# trig3_board_de0-nano.net
KiCad netlist of a schematic drawn in EAGLE
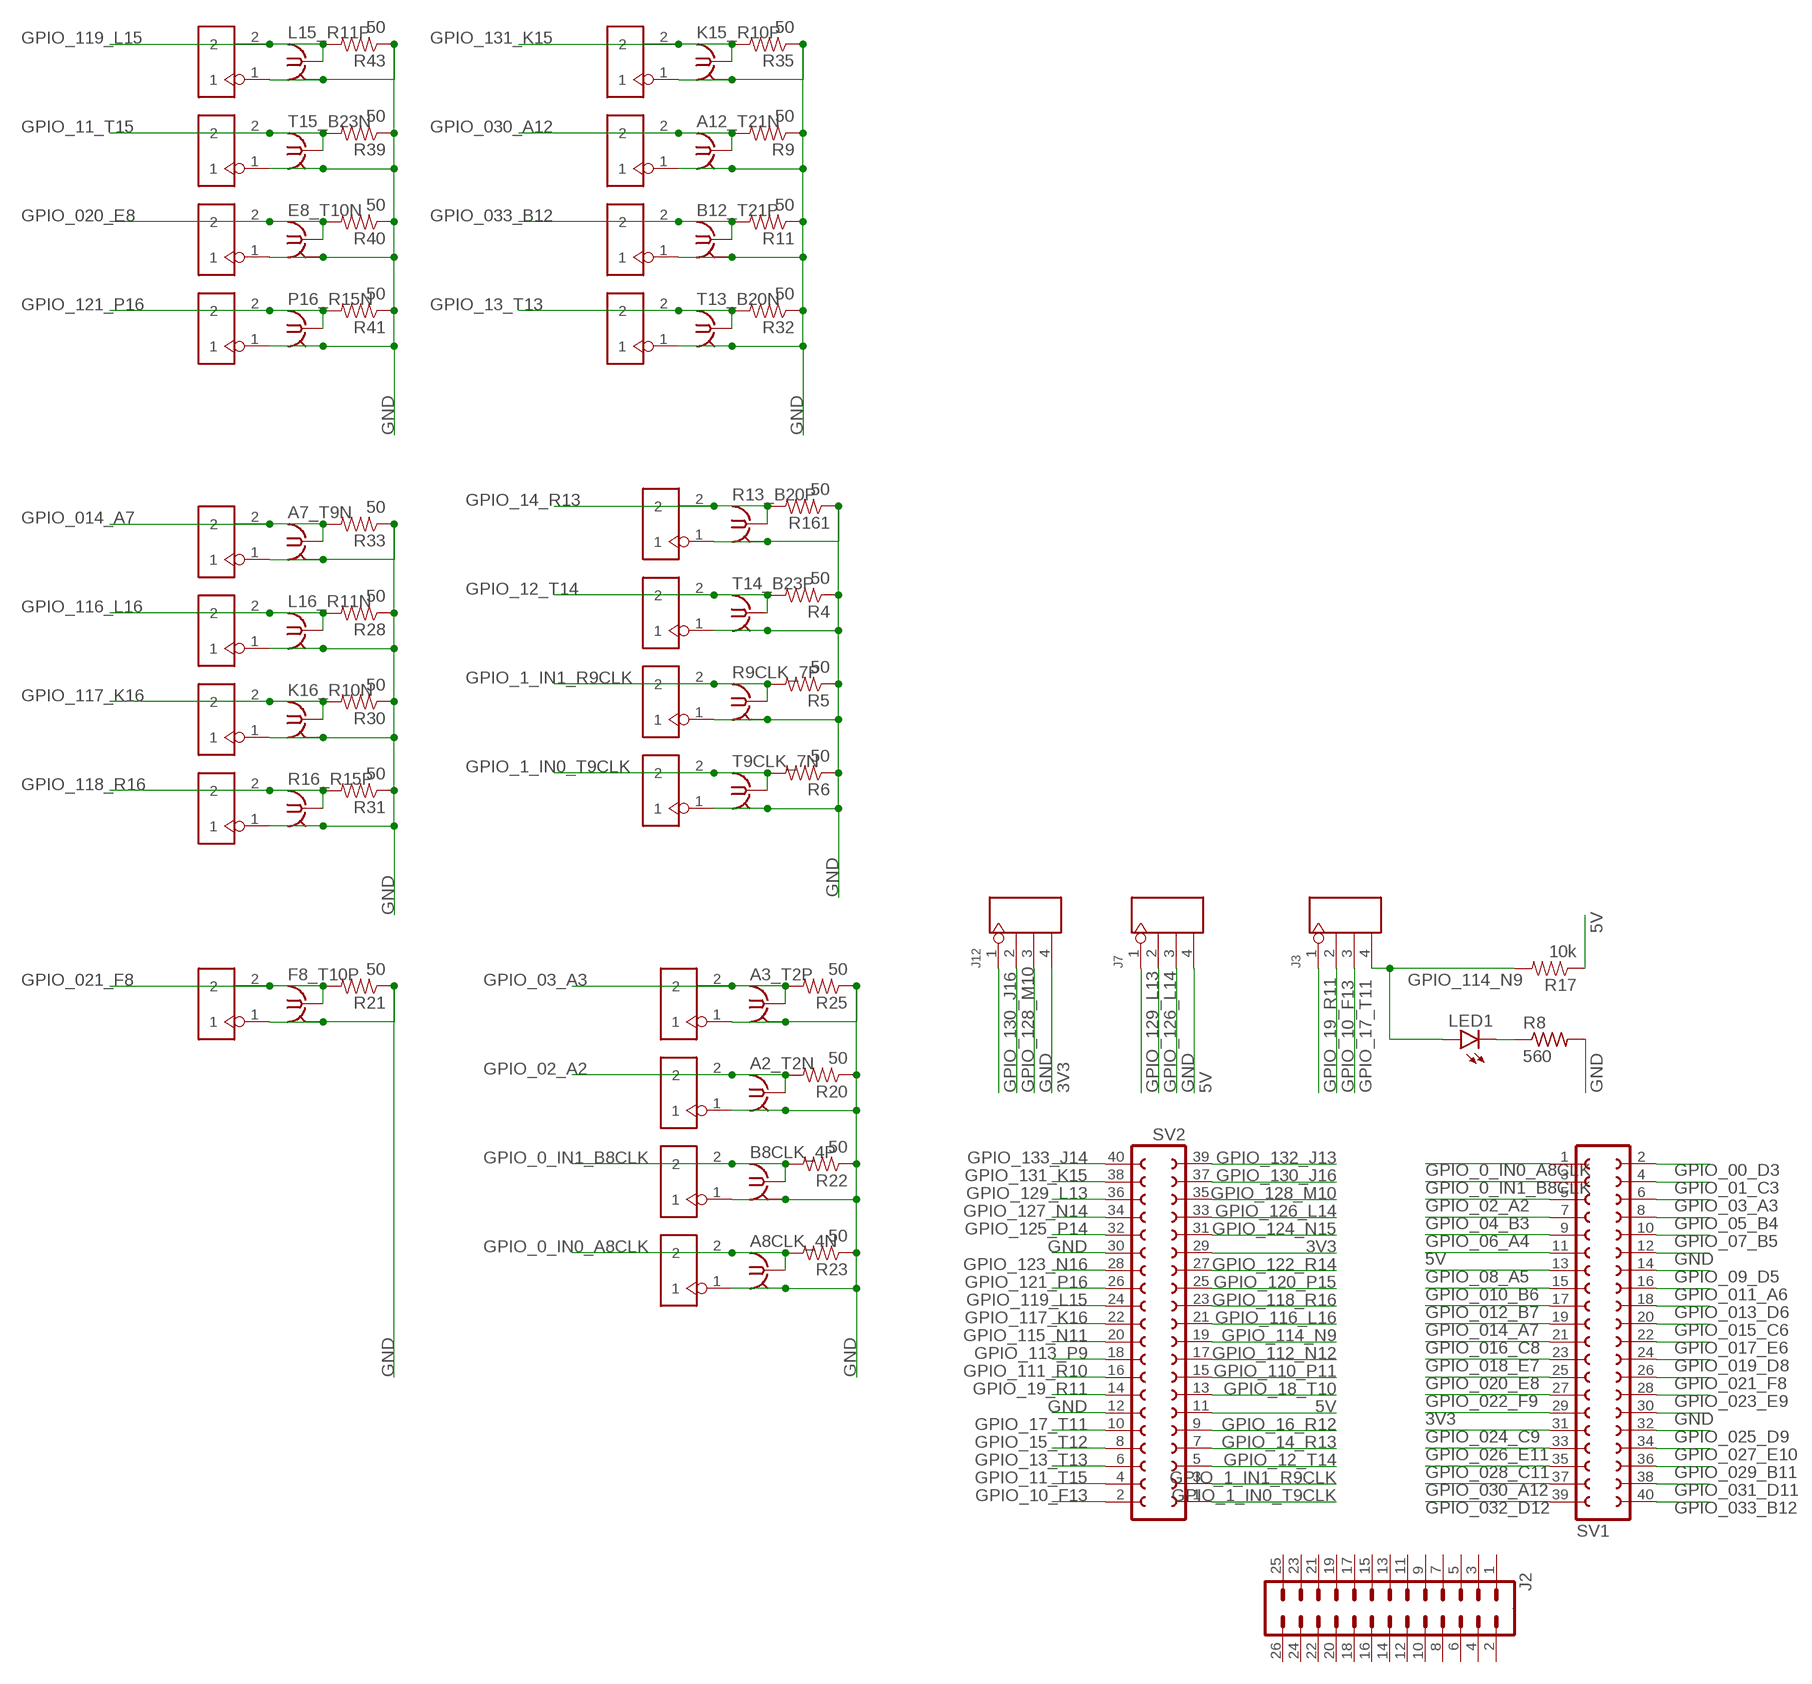
[diagram p0: schematic, sheet 1, part 1 of 2]
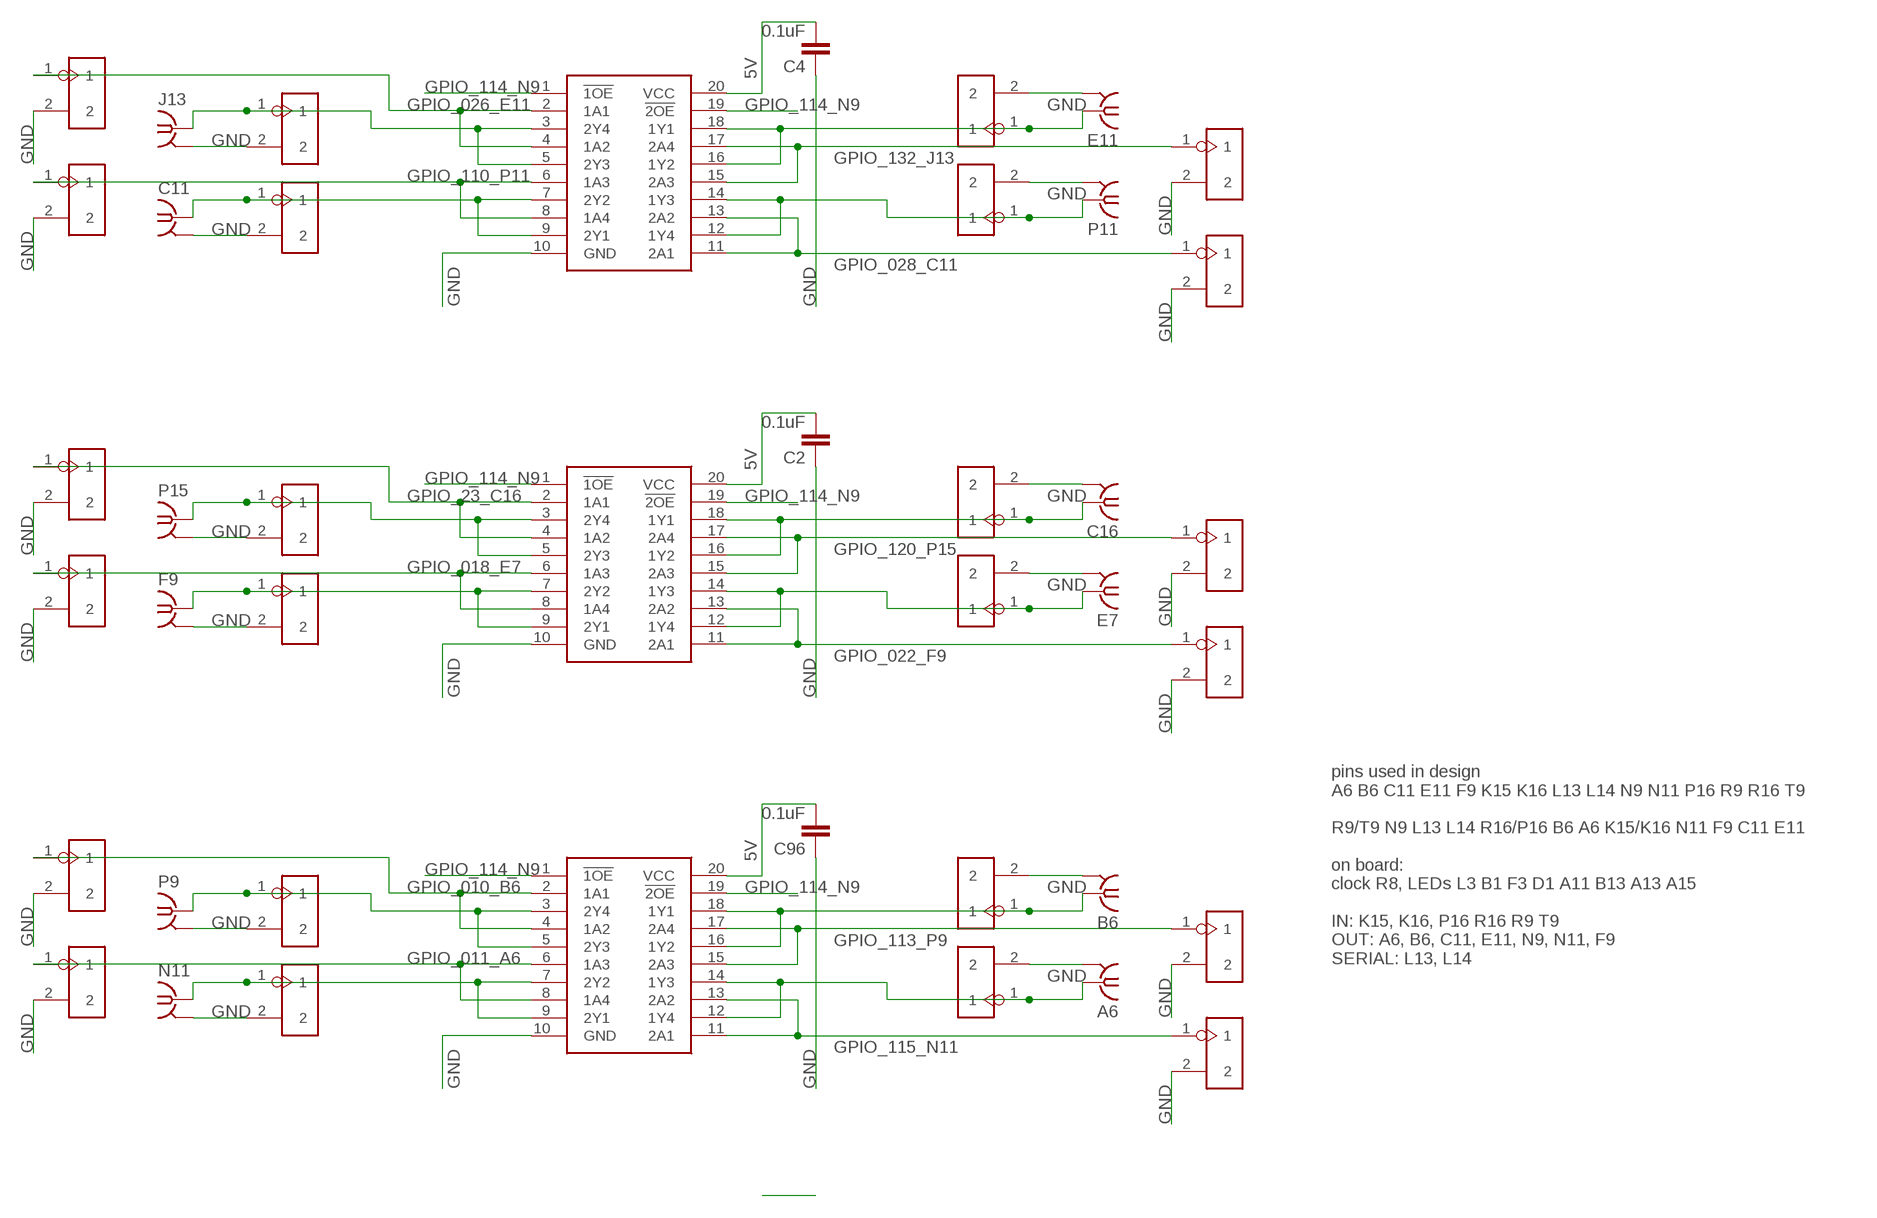
[diagram p1: schematic, sheet 1, part 2 of 2]

(export (version "E")
  (design (tool "Eeschema 10.0.6"))
  (components
    (comp (ref "A2_T2N")
      (value "BU-SMB-V")
      (footprint "eagle-import:BU-SMB-V")
      (libsource (lib "eagle-import") (part "BU-SMB-V"))
    )
    (comp (ref "A3_T2P")
      (value "BU-SMB-V")
      (footprint "eagle-import:BU-SMB-V")
      (libsource (lib "eagle-import") (part "BU-SMB-V"))
    )
    (comp (ref "A6")
      (value "BU-SMB-V")
      (footprint "eagle-import:BU-SMB-V")
      (libsource (lib "eagle-import") (part "BU-SMB-V"))
    )
    (comp (ref "A7_T9N")
      (value "BU-SMB-V")
      (footprint "eagle-import:BU-SMB-V")
      (libsource (lib "eagle-import") (part "BU-SMB-V"))
    )
    (comp (ref "A8CLK_4N")
      (value "BU-SMB-V")
      (footprint "eagle-import:BU-SMB-V")
      (libsource (lib "eagle-import") (part "BU-SMB-V"))
    )
    (comp (ref "A12_T21N")
      (value "BU-SMB-V")
      (footprint "eagle-import:BU-SMB-V")
      (libsource (lib "eagle-import") (part "BU-SMB-V"))
    )
    (comp (ref "B6")
      (value "BU-SMB-V")
      (footprint "eagle-import:BU-SMB-V")
      (libsource (lib "eagle-import") (part "BU-SMB-V"))
    )
    (comp (ref "B8CLK_4P")
      (value "BU-SMB-V")
      (footprint "eagle-import:BU-SMB-V")
      (libsource (lib "eagle-import") (part "BU-SMB-V"))
    )
    (comp (ref "B12_T21P")
      (value "BU-SMB-V")
      (footprint "eagle-import:BU-SMB-V")
      (libsource (lib "eagle-import") (part "BU-SMB-V"))
    )
    (comp (ref "C2")
      (value "0.1uF")
      (footprint "eagle-import:0805")
      (libsource (lib "eagle-import") (part "CAP0805"))
    )
    (comp (ref "C4")
      (value "0.1uF")
      (footprint "eagle-import:0805")
      (libsource (lib "eagle-import") (part "CAP0805"))
    )
    (comp (ref "C11")
      (value "BU-SMB-V")
      (footprint "eagle-import:BU-SMB-V")
      (libsource (lib "eagle-import") (part "BU-SMB-V"))
    )
    (comp (ref "C16")
      (value "BU-SMB-V")
      (footprint "eagle-import:BU-SMB-V")
      (libsource (lib "eagle-import") (part "BU-SMB-V"))
    )
    (comp (ref "C96")
      (value "0.1uF")
      (footprint "eagle-import:0805")
      (libsource (lib "eagle-import") (part "CAP0805"))
    )
    (comp (ref "E7")
      (value "BU-SMB-V")
      (footprint "eagle-import:BU-SMB-V")
      (libsource (lib "eagle-import") (part "BU-SMB-V"))
    )
    (comp (ref "E8_T10N")
      (value "BU-SMB-V")
      (footprint "eagle-import:BU-SMB-V")
      (libsource (lib "eagle-import") (part "BU-SMB-V"))
    )
    (comp (ref "E11")
      (value "BU-SMB-V")
      (footprint "eagle-import:BU-SMB-V")
      (libsource (lib "eagle-import") (part "BU-SMB-V"))
    )
    (comp (ref "F8_T10P")
      (value "BU-SMB-V")
      (footprint "eagle-import:BU-SMB-V")
      (libsource (lib "eagle-import") (part "BU-SMB-V"))
    )
    (comp (ref "F9")
      (value "BU-SMB-V")
      (footprint "eagle-import:BU-SMB-V")
      (libsource (lib "eagle-import") (part "BU-SMB-V"))
    )
    (comp (ref "J2")
      (value "M13X22X13")
      (footprint "eagle-import:2X13")
      (libsource (lib "eagle-import") (part "M13X22X13"))
    )
    (comp (ref "J3")
      (value "4p-2.54")
      (footprint "eagle-import:H4-2.54")
      (fields (field (name "MPN") "F185-1104A1BSYA1"))
      (libsource (lib "eagle-import") (part "DIP-BLACK-FEMALE-HEADER-VERT(4P-2.54)"))
    )
    (comp (ref "J4")
      (value "2p-2.54")
      (footprint "eagle-import:H2-2.54")
      (fields (field (name "MPN") "P125-1102A0BS116A1"))
      (libsource (lib "eagle-import") (part "DIP-BLACK-MALE-HEADER-VERT(2P-2.54)"))
    )
    (comp (ref "J5")
      (value "2p-2.54")
      (footprint "eagle-import:H2-2.54")
      (fields (field (name "MPN") "P125-1102A0BS116A1"))
      (libsource (lib "eagle-import") (part "DIP-BLACK-MALE-HEADER-VERT(2P-2.54)"))
    )
    (comp (ref "J6")
      (value "2p-2.54")
      (footprint "eagle-import:H2-2.54")
      (fields (field (name "MPN") "P125-1102A0BS116A1"))
      (libsource (lib "eagle-import") (part "DIP-BLACK-MALE-HEADER-VERT(2P-2.54)"))
    )
    (comp (ref "J7")
      (value "4p-2.54")
      (footprint "eagle-import:H4-2.54")
      (fields (field (name "MPN") "F185-1104A1BSYA1"))
      (libsource (lib "eagle-import") (part "DIP-BLACK-FEMALE-HEADER-VERT(4P-2.54)"))
    )
    (comp (ref "J12")
      (value "4p-2.54")
      (footprint "eagle-import:H4-2.54")
      (fields (field (name "MPN") "F185-1104A1BSYA1"))
      (libsource (lib "eagle-import") (part "DIP-BLACK-FEMALE-HEADER-VERT(4P-2.54)"))
    )
    (comp (ref "J13")
      (value "BU-SMB-V")
      (footprint "eagle-import:BU-SMB-V")
      (libsource (lib "eagle-import") (part "BU-SMB-V"))
    )
    (comp (ref "J17")
      (value "2p-2.54")
      (footprint "eagle-import:H2-2.54")
      (fields (field (name "MPN") "P125-1102A0BS116A1"))
      (libsource (lib "eagle-import") (part "DIP-BLACK-MALE-HEADER-VERT(2P-2.54)"))
    )
    (comp (ref "J18")
      (value "2p-2.54")
      (footprint "eagle-import:H2-2.54")
      (fields (field (name "MPN") "P125-1102A0BS116A1"))
      (libsource (lib "eagle-import") (part "DIP-BLACK-MALE-HEADER-VERT(2P-2.54)"))
    )
    (comp (ref "J22")
      (value "2p-2.54")
      (footprint "eagle-import:H2-2.54")
      (fields (field (name "MPN") "P125-1102A0BS116A1"))
      (libsource (lib "eagle-import") (part "DIP-BLACK-MALE-HEADER-VERT(2P-2.54)"))
    )
    (comp (ref "J23")
      (value "2p-2.54")
      (footprint "eagle-import:H2-2.54")
      (fields (field (name "MPN") "P125-1102A0BS116A1"))
      (libsource (lib "eagle-import") (part "DIP-BLACK-MALE-HEADER-VERT(2P-2.54)"))
    )
    (comp (ref "J24")
      (value "2p-2.54")
      (footprint "eagle-import:H2-2.54")
      (fields (field (name "MPN") "P125-1102A0BS116A1"))
      (libsource (lib "eagle-import") (part "DIP-BLACK-MALE-HEADER-VERT(2P-2.54)"))
    )
    (comp (ref "J25")
      (value "2p-2.54")
      (footprint "eagle-import:H2-2.54")
      (fields (field (name "MPN") "P125-1102A0BS116A1"))
      (libsource (lib "eagle-import") (part "DIP-BLACK-MALE-HEADER-VERT(2P-2.54)"))
    )
    (comp (ref "J32")
      (value "2p-2.54")
      (footprint "eagle-import:H2-2.54")
      (fields (field (name "MPN") "P125-1102A0BS116A1"))
      (libsource (lib "eagle-import") (part "DIP-BLACK-MALE-HEADER-VERT(2P-2.54)"))
    )
    (comp (ref "J33")
      (value "2p-2.54")
      (footprint "eagle-import:H2-2.54")
      (fields (field (name "MPN") "P125-1102A0BS116A1"))
      (libsource (lib "eagle-import") (part "DIP-BLACK-MALE-HEADER-VERT(2P-2.54)"))
    )
    (comp (ref "J34")
      (value "2p-2.54")
      (footprint "eagle-import:H2-2.54")
      (fields (field (name "MPN") "P125-1102A0BS116A1"))
      (libsource (lib "eagle-import") (part "DIP-BLACK-MALE-HEADER-VERT(2P-2.54)"))
    )
    (comp (ref "J35")
      (value "2p-2.54")
      (footprint "eagle-import:H2-2.54")
      (fields (field (name "MPN") "P125-1102A0BS116A1"))
      (libsource (lib "eagle-import") (part "DIP-BLACK-MALE-HEADER-VERT(2P-2.54)"))
    )
    (comp (ref "J36")
      (value "2p-2.54")
      (footprint "eagle-import:H2-2.54")
      (fields (field (name "MPN") "P125-1102A0BS116A1"))
      (libsource (lib "eagle-import") (part "DIP-BLACK-MALE-HEADER-VERT(2P-2.54)"))
    )
    (comp (ref "J37")
      (value "2p-2.54")
      (footprint "eagle-import:H2-2.54")
      (fields (field (name "MPN") "P125-1102A0BS116A1"))
      (libsource (lib "eagle-import") (part "DIP-BLACK-MALE-HEADER-VERT(2P-2.54)"))
    )
    (comp (ref "J38")
      (value "2p-2.54")
      (footprint "eagle-import:H2-2.54")
      (fields (field (name "MPN") "P125-1102A0BS116A1"))
      (libsource (lib "eagle-import") (part "DIP-BLACK-MALE-HEADER-VERT(2P-2.54)"))
    )
    (comp (ref "J39")
      (value "2p-2.54")
      (footprint "eagle-import:H2-2.54")
      (fields (field (name "MPN") "P125-1102A0BS116A1"))
      (libsource (lib "eagle-import") (part "DIP-BLACK-MALE-HEADER-VERT(2P-2.54)"))
    )
    (comp (ref "J40")
      (value "2p-2.54")
      (footprint "eagle-import:H2-2.54")
      (fields (field (name "MPN") "P125-1102A0BS116A1"))
      (libsource (lib "eagle-import") (part "DIP-BLACK-MALE-HEADER-VERT(2P-2.54)"))
    )
    (comp (ref "J41")
      (value "2p-2.54")
      (footprint "eagle-import:H2-2.54")
      (fields (field (name "MPN") "P125-1102A0BS116A1"))
      (libsource (lib "eagle-import") (part "DIP-BLACK-MALE-HEADER-VERT(2P-2.54)"))
    )
    (comp (ref "J42")
      (value "2p-2.54")
      (footprint "eagle-import:H2-2.54")
      (fields (field (name "MPN") "P125-1102A0BS116A1"))
      (libsource (lib "eagle-import") (part "DIP-BLACK-MALE-HEADER-VERT(2P-2.54)"))
    )
    (comp (ref "J43")
      (value "2p-2.54")
      (footprint "eagle-import:H2-2.54")
      (fields (field (name "MPN") "P125-1102A0BS116A1"))
      (libsource (lib "eagle-import") (part "DIP-BLACK-MALE-HEADER-VERT(2P-2.54)"))
    )
    (comp (ref "K15_R10P")
      (value "BU-SMB-V")
      (footprint "eagle-import:BU-SMB-V")
      (libsource (lib "eagle-import") (part "BU-SMB-V"))
    )
    (comp (ref "K16_R10N")
      (value "BU-SMB-V")
      (footprint "eagle-import:BU-SMB-V")
      (libsource (lib "eagle-import") (part "BU-SMB-V"))
    )
    (comp (ref "L15_R11P")
      (value "BU-SMB-V")
      (footprint "eagle-import:BU-SMB-V")
      (libsource (lib "eagle-import") (part "BU-SMB-V"))
    )
    (comp (ref "L16_R11N")
      (value "BU-SMB-V")
      (footprint "eagle-import:BU-SMB-V")
      (libsource (lib "eagle-import") (part "BU-SMB-V"))
    )
    (comp (ref "LED1")
      (value "red")
      (footprint "eagle-import:CHIP-LED0805")
      (libsource (lib "eagle-import") (part "LEDCHIP-LED0805"))
    )
    (comp (ref "N11")
      (value "BU-SMB-V")
      (footprint "eagle-import:BU-SMB-V")
      (libsource (lib "eagle-import") (part "BU-SMB-V"))
    )
    (comp (ref "OJ41")
      (value "2p-2.54")
      (footprint "eagle-import:H2-2.54")
      (fields (field (name "MPN") "P125-1102A0BS116A1"))
      (libsource (lib "eagle-import") (part "DIP-BLACK-MALE-HEADER-VERT(2P-2.54)"))
    )
    (comp (ref "OJ42")
      (value "2p-2.54")
      (footprint "eagle-import:H2-2.54")
      (fields (field (name "MPN") "P125-1102A0BS116A1"))
      (libsource (lib "eagle-import") (part "DIP-BLACK-MALE-HEADER-VERT(2P-2.54)"))
    )
    (comp (ref "OJ43")
      (value "2p-2.54")
      (footprint "eagle-import:H2-2.54")
      (fields (field (name "MPN") "P125-1102A0BS116A1"))
      (libsource (lib "eagle-import") (part "DIP-BLACK-MALE-HEADER-VERT(2P-2.54)"))
    )
    (comp (ref "OJ44")
      (value "2p-2.54")
      (footprint "eagle-import:H2-2.54")
      (fields (field (name "MPN") "P125-1102A0BS116A1"))
      (libsource (lib "eagle-import") (part "DIP-BLACK-MALE-HEADER-VERT(2P-2.54)"))
    )
    (comp (ref "OJ45")
      (value "2p-2.54")
      (footprint "eagle-import:H2-2.54")
      (fields (field (name "MPN") "P125-1102A0BS116A1"))
      (libsource (lib "eagle-import") (part "DIP-BLACK-MALE-HEADER-VERT(2P-2.54)"))
    )
    (comp (ref "OJ46")
      (value "2p-2.54")
      (footprint "eagle-import:H2-2.54")
      (fields (field (name "MPN") "P125-1102A0BS116A1"))
      (libsource (lib "eagle-import") (part "DIP-BLACK-MALE-HEADER-VERT(2P-2.54)"))
    )
    (comp (ref "OJ47")
      (value "2p-2.54")
      (footprint "eagle-import:H2-2.54")
      (fields (field (name "MPN") "P125-1102A0BS116A1"))
      (libsource (lib "eagle-import") (part "DIP-BLACK-MALE-HEADER-VERT(2P-2.54)"))
    )
    (comp (ref "OJ48")
      (value "2p-2.54")
      (footprint "eagle-import:H2-2.54")
      (fields (field (name "MPN") "P125-1102A0BS116A1"))
      (libsource (lib "eagle-import") (part "DIP-BLACK-MALE-HEADER-VERT(2P-2.54)"))
    )
    (comp (ref "OJ57")
      (value "2p-2.54")
      (footprint "eagle-import:H2-2.54")
      (fields (field (name "MPN") "P125-1102A0BS116A1"))
      (libsource (lib "eagle-import") (part "DIP-BLACK-MALE-HEADER-VERT(2P-2.54)"))
    )
    (comp (ref "OJ58")
      (value "2p-2.54")
      (footprint "eagle-import:H2-2.54")
      (fields (field (name "MPN") "P125-1102A0BS116A1"))
      (libsource (lib "eagle-import") (part "DIP-BLACK-MALE-HEADER-VERT(2P-2.54)"))
    )
    (comp (ref "OJ59")
      (value "2p-2.54")
      (footprint "eagle-import:H2-2.54")
      (fields (field (name "MPN") "P125-1102A0BS116A1"))
      (libsource (lib "eagle-import") (part "DIP-BLACK-MALE-HEADER-VERT(2P-2.54)"))
    )
    (comp (ref "OJ60")
      (value "2p-2.54")
      (footprint "eagle-import:H2-2.54")
      (fields (field (name "MPN") "P125-1102A0BS116A1"))
      (libsource (lib "eagle-import") (part "DIP-BLACK-MALE-HEADER-VERT(2P-2.54)"))
    )
    (comp (ref "OJ61")
      (value "2p-2.54")
      (footprint "eagle-import:H2-2.54")
      (fields (field (name "MPN") "P125-1102A0BS116A1"))
      (libsource (lib "eagle-import") (part "DIP-BLACK-MALE-HEADER-VERT(2P-2.54)"))
    )
    (comp (ref "OJ62")
      (value "2p-2.54")
      (footprint "eagle-import:H2-2.54")
      (fields (field (name "MPN") "P125-1102A0BS116A1"))
      (libsource (lib "eagle-import") (part "DIP-BLACK-MALE-HEADER-VERT(2P-2.54)"))
    )
    (comp (ref "OJ63")
      (value "2p-2.54")
      (footprint "eagle-import:H2-2.54")
      (fields (field (name "MPN") "P125-1102A0BS116A1"))
      (libsource (lib "eagle-import") (part "DIP-BLACK-MALE-HEADER-VERT(2P-2.54)"))
    )
    (comp (ref "OJ64")
      (value "2p-2.54")
      (footprint "eagle-import:H2-2.54")
      (fields (field (name "MPN") "P125-1102A0BS116A1"))
      (libsource (lib "eagle-import") (part "DIP-BLACK-MALE-HEADER-VERT(2P-2.54)"))
    )
    (comp (ref "OJ73")
      (value "2p-2.54")
      (footprint "eagle-import:H2-2.54")
      (fields (field (name "MPN") "P125-1102A0BS116A1"))
      (libsource (lib "eagle-import") (part "DIP-BLACK-MALE-HEADER-VERT(2P-2.54)"))
    )
    (comp (ref "OJ74")
      (value "2p-2.54")
      (footprint "eagle-import:H2-2.54")
      (fields (field (name "MPN") "P125-1102A0BS116A1"))
      (libsource (lib "eagle-import") (part "DIP-BLACK-MALE-HEADER-VERT(2P-2.54)"))
    )
    (comp (ref "OJ75")
      (value "2p-2.54")
      (footprint "eagle-import:H2-2.54")
      (fields (field (name "MPN") "P125-1102A0BS116A1"))
      (libsource (lib "eagle-import") (part "DIP-BLACK-MALE-HEADER-VERT(2P-2.54)"))
    )
    (comp (ref "OJ76")
      (value "2p-2.54")
      (footprint "eagle-import:H2-2.54")
      (fields (field (name "MPN") "P125-1102A0BS116A1"))
      (libsource (lib "eagle-import") (part "DIP-BLACK-MALE-HEADER-VERT(2P-2.54)"))
    )
    (comp (ref "OJ77")
      (value "2p-2.54")
      (footprint "eagle-import:H2-2.54")
      (fields (field (name "MPN") "P125-1102A0BS116A1"))
      (libsource (lib "eagle-import") (part "DIP-BLACK-MALE-HEADER-VERT(2P-2.54)"))
    )
    (comp (ref "OJ78")
      (value "2p-2.54")
      (footprint "eagle-import:H2-2.54")
      (fields (field (name "MPN") "P125-1102A0BS116A1"))
      (libsource (lib "eagle-import") (part "DIP-BLACK-MALE-HEADER-VERT(2P-2.54)"))
    )
    (comp (ref "OJ79")
      (value "2p-2.54")
      (footprint "eagle-import:H2-2.54")
      (fields (field (name "MPN") "P125-1102A0BS116A1"))
      (libsource (lib "eagle-import") (part "DIP-BLACK-MALE-HEADER-VERT(2P-2.54)"))
    )
    (comp (ref "OJ80")
      (value "2p-2.54")
      (footprint "eagle-import:H2-2.54")
      (fields (field (name "MPN") "P125-1102A0BS116A1"))
      (libsource (lib "eagle-import") (part "DIP-BLACK-MALE-HEADER-VERT(2P-2.54)"))
    )
    (comp (ref "P9")
      (value "BU-SMB-V")
      (footprint "eagle-import:BU-SMB-V")
      (libsource (lib "eagle-import") (part "BU-SMB-V"))
    )
    (comp (ref "P11")
      (value "BU-SMB-V")
      (footprint "eagle-import:BU-SMB-V")
      (libsource (lib "eagle-import") (part "BU-SMB-V"))
    )
    (comp (ref "P15")
      (value "BU-SMB-V")
      (footprint "eagle-import:BU-SMB-V")
      (libsource (lib "eagle-import") (part "BU-SMB-V"))
    )
    (comp (ref "P16_R15N")
      (value "BU-SMB-V")
      (footprint "eagle-import:BU-SMB-V")
      (libsource (lib "eagle-import") (part "BU-SMB-V"))
    )
    (comp (ref "R4")
      (value "50")
      (footprint "eagle-import:AXIAL-0.3")
      (libsource (lib "eagle-import") (part "RESISTORAXIAL-0.3"))
    )
    (comp (ref "R5")
      (value "50")
      (footprint "eagle-import:AXIAL-0.3")
      (libsource (lib "eagle-import") (part "RESISTORAXIAL-0.3"))
    )
    (comp (ref "R6")
      (value "50")
      (footprint "eagle-import:AXIAL-0.3")
      (libsource (lib "eagle-import") (part "RESISTORAXIAL-0.3"))
    )
    (comp (ref "R8")
      (value "560")
      (footprint "eagle-import:R0805")
      (libsource (lib "eagle-import") (part "R-US_R0805"))
    )
    (comp (ref "R9")
      (value "50")
      (footprint "eagle-import:AXIAL-0.3")
      (libsource (lib "eagle-import") (part "RESISTORAXIAL-0.3"))
    )
    (comp (ref "R9CLK_7P")
      (value "BU-SMB-V")
      (footprint "eagle-import:BU-SMB-V")
      (libsource (lib "eagle-import") (part "BU-SMB-V"))
    )
    (comp (ref "R11")
      (value "50")
      (footprint "eagle-import:AXIAL-0.3")
      (libsource (lib "eagle-import") (part "RESISTORAXIAL-0.3"))
    )
    (comp (ref "R13_B20P")
      (value "BU-SMB-V")
      (footprint "eagle-import:BU-SMB-V")
      (libsource (lib "eagle-import") (part "BU-SMB-V"))
    )
    (comp (ref "R16_R15P")
      (value "BU-SMB-V")
      (footprint "eagle-import:BU-SMB-V")
      (libsource (lib "eagle-import") (part "BU-SMB-V"))
    )
    (comp (ref "R17")
      (value "10k")
      (footprint "eagle-import:AXIAL-0.3")
      (libsource (lib "eagle-import") (part "RESISTORAXIAL-0.3"))
    )
    (comp (ref "R20")
      (value "50")
      (footprint "eagle-import:AXIAL-0.3")
      (libsource (lib "eagle-import") (part "RESISTORAXIAL-0.3"))
    )
    (comp (ref "R21")
      (value "50")
      (footprint "eagle-import:AXIAL-0.3")
      (libsource (lib "eagle-import") (part "RESISTORAXIAL-0.3"))
    )
    (comp (ref "R22")
      (value "50")
      (footprint "eagle-import:AXIAL-0.3")
      (libsource (lib "eagle-import") (part "RESISTORAXIAL-0.3"))
    )
    (comp (ref "R23")
      (value "50")
      (footprint "eagle-import:AXIAL-0.3")
      (libsource (lib "eagle-import") (part "RESISTORAXIAL-0.3"))
    )
    (comp (ref "R25")
      (value "50")
      (footprint "eagle-import:AXIAL-0.3")
      (libsource (lib "eagle-import") (part "RESISTORAXIAL-0.3"))
    )
    (comp (ref "R28")
      (value "50")
      (footprint "eagle-import:AXIAL-0.3")
      (libsource (lib "eagle-import") (part "RESISTORAXIAL-0.3"))
    )
    (comp (ref "R30")
      (value "50")
      (footprint "eagle-import:AXIAL-0.3")
      (libsource (lib "eagle-import") (part "RESISTORAXIAL-0.3"))
    )
    (comp (ref "R31")
      (value "50")
      (footprint "eagle-import:AXIAL-0.3")
      (libsource (lib "eagle-import") (part "RESISTORAXIAL-0.3"))
    )
    (comp (ref "R32")
      (value "50")
      (footprint "eagle-import:AXIAL-0.3")
      (libsource (lib "eagle-import") (part "RESISTORAXIAL-0.3"))
    )
    (comp (ref "R33")
      (value "50")
      (footprint "eagle-import:AXIAL-0.3")
      (libsource (lib "eagle-import") (part "RESISTORAXIAL-0.3"))
    )
    (comp (ref "R35")
      (value "50")
      (footprint "eagle-import:AXIAL-0.3")
      (libsource (lib "eagle-import") (part "RESISTORAXIAL-0.3"))
    )
    (comp (ref "R39")
      (value "50")
      (footprint "eagle-import:AXIAL-0.3")
      (libsource (lib "eagle-import") (part "RESISTORAXIAL-0.3"))
    )
    (comp (ref "R40")
      (value "50")
      (footprint "eagle-import:AXIAL-0.3")
      (libsource (lib "eagle-import") (part "RESISTORAXIAL-0.3"))
    )
    (comp (ref "R41")
      (value "50")
      (footprint "eagle-import:AXIAL-0.3")
      (libsource (lib "eagle-import") (part "RESISTORAXIAL-0.3"))
    )
    (comp (ref "R43")
      (value "50")
      (footprint "eagle-import:AXIAL-0.3")
      (libsource (lib "eagle-import") (part "RESISTORAXIAL-0.3"))
    )
    (comp (ref "R161")
      (value "50")
      (footprint "eagle-import:AXIAL-0.3")
      (libsource (lib "eagle-import") (part "RESISTORAXIAL-0.3"))
    )
    (comp (ref "SV1")
      (value "FE20-2")
      (footprint "eagle-import:FE20-2")
      (libsource (lib "eagle-import") (part "FE20-2"))
    )
    (comp (ref "SV2")
      (value "FE20-2")
      (footprint "eagle-import:FE20-2")
      (libsource (lib "eagle-import") (part "FE20-2"))
    )
    (comp (ref "T9CLK_7N")
      (value "BU-SMB-V")
      (footprint "eagle-import:BU-SMB-V")
      (libsource (lib "eagle-import") (part "BU-SMB-V"))
    )
    (comp (ref "T13_B20N")
      (value "BU-SMB-V")
      (footprint "eagle-import:BU-SMB-V")
      (libsource (lib "eagle-import") (part "BU-SMB-V"))
    )
    (comp (ref "T14_B23P")
      (value "BU-SMB-V")
      (footprint "eagle-import:BU-SMB-V")
      (libsource (lib "eagle-import") (part "BU-SMB-V"))
    )
    (comp (ref "T15_B23N")
      (value "BU-SMB-V")
      (footprint "eagle-import:BU-SMB-V")
      (libsource (lib "eagle-import") (part "BU-SMB-V"))
    )
    (comp (ref "VSLUE5")
      (value "SN74ACT244DW")
      (footprint "eagle-import:SOIC127P1030X265-20N")
      (fields (field (name "RS_PART_NUMBER") "4363169"))
      (libsource (lib "eagle-import") (part "SN74ACT244DW"))
    )
    (comp (ref "VSLUE7")
      (value "SN74ACT244DW")
      (footprint "eagle-import:SOIC127P1030X265-20N")
      (fields (field (name "RS_PART_NUMBER") "4363169"))
      (libsource (lib "eagle-import") (part "SN74ACT244DW"))
    )
    (comp (ref "VSLUE9")
      (value "SN74ACT244DW")
      (footprint "eagle-import:SOIC127P1030X265-20N")
      (fields (field (name "RS_PART_NUMBER") "4363169"))
      (libsource (lib "eagle-import") (part "SN74ACT244DW"))
    )
  )
  (nets
    (net (code "1") (name "/3V3") (class "Default")
      (node (ref "J12") (pin "4") (pinfunction "P$4_4") (pintype "bidirectional"))
      (node (ref "SV1") (pin "29") (pinfunction "29_29") (pintype "passive"))
      (node (ref "SV2") (pin "29") (pinfunction "29_29") (pintype "passive"))
    )
    (net (code "2") (name "/5V") (class "Default")
      (node (ref "C2") (pin "2") (pinfunction "2_2") (pintype "passive"))
      (node (ref "C4") (pin "2") (pinfunction "2_2") (pintype "passive"))
      (node (ref "C96") (pin "2") (pinfunction "2_2") (pintype "passive"))
      (node (ref "J7") (pin "4") (pinfunction "P$4_4") (pintype "bidirectional"))
      (node (ref "R17") (pin "P$1") (pinfunction "1_P$1") (pintype "passive"))
      (node (ref "SV1") (pin "11") (pinfunction "11_11") (pintype "passive"))
      (node (ref "SV2") (pin "11") (pinfunction "11_11") (pintype "passive"))
      (node (ref "VSLUE5") (pin "20") (pinfunction "VCC_20") (pintype "power_in"))
      (node (ref "VSLUE7") (pin "20") (pinfunction "VCC_20") (pintype "power_in"))
      (node (ref "VSLUE9") (pin "20") (pinfunction "VCC_20") (pintype "power_in"))
    )
    (net (code "3") (name "/GND") (class "Default")
      (node (ref "A12_T21N") (pin "2") (pinfunction "2_2") (pintype "passive"))
      (node (ref "A12_T21N") (pin "3") (pinfunction "2_3") (pintype "passive"))
      (node (ref "A12_T21N") (pin "4") (pinfunction "2_4") (pintype "passive"))
      (node (ref "A12_T21N") (pin "5") (pinfunction "2_5") (pintype "passive"))
      (node (ref "A2_T2N") (pin "2") (pinfunction "2_2") (pintype "passive"))
      (node (ref "A2_T2N") (pin "3") (pinfunction "2_3") (pintype "passive"))
      (node (ref "A2_T2N") (pin "4") (pinfunction "2_4") (pintype "passive"))
      (node (ref "A2_T2N") (pin "5") (pinfunction "2_5") (pintype "passive"))
      (node (ref "A3_T2P") (pin "2") (pinfunction "2_2") (pintype "passive"))
      (node (ref "A3_T2P") (pin "3") (pinfunction "2_3") (pintype "passive"))
      (node (ref "A3_T2P") (pin "4") (pinfunction "2_4") (pintype "passive"))
      (node (ref "A3_T2P") (pin "5") (pinfunction "2_5") (pintype "passive"))
      (node (ref "A6") (pin "2") (pinfunction "2_2") (pintype "passive"))
      (node (ref "A6") (pin "3") (pinfunction "2_3") (pintype "passive"))
      (node (ref "A6") (pin "4") (pinfunction "2_4") (pintype "passive"))
      (node (ref "A6") (pin "5") (pinfunction "2_5") (pintype "passive"))
      (node (ref "A7_T9N") (pin "2") (pinfunction "2_2") (pintype "passive"))
      (node (ref "A7_T9N") (pin "3") (pinfunction "2_3") (pintype "passive"))
      (node (ref "A7_T9N") (pin "4") (pinfunction "2_4") (pintype "passive"))
      (node (ref "A7_T9N") (pin "5") (pinfunction "2_5") (pintype "passive"))
      (node (ref "A8CLK_4N") (pin "2") (pinfunction "2_2") (pintype "passive"))
      (node (ref "A8CLK_4N") (pin "3") (pinfunction "2_3") (pintype "passive"))
      (node (ref "A8CLK_4N") (pin "4") (pinfunction "2_4") (pintype "passive"))
      (node (ref "A8CLK_4N") (pin "5") (pinfunction "2_5") (pintype "passive"))
      (node (ref "B12_T21P") (pin "2") (pinfunction "2_2") (pintype "passive"))
      (node (ref "B12_T21P") (pin "3") (pinfunction "2_3") (pintype "passive"))
      (node (ref "B12_T21P") (pin "4") (pinfunction "2_4") (pintype "passive"))
      (node (ref "B12_T21P") (pin "5") (pinfunction "2_5") (pintype "passive"))
      (node (ref "B6") (pin "2") (pinfunction "2_2") (pintype "passive"))
      (node (ref "B6") (pin "3") (pinfunction "2_3") (pintype "passive"))
      (node (ref "B6") (pin "4") (pinfunction "2_4") (pintype "passive"))
      (node (ref "B6") (pin "5") (pinfunction "2_5") (pintype "passive"))
      (node (ref "B8CLK_4P") (pin "2") (pinfunction "2_2") (pintype "passive"))
      (node (ref "B8CLK_4P") (pin "3") (pinfunction "2_3") (pintype "passive"))
      (node (ref "B8CLK_4P") (pin "4") (pinfunction "2_4") (pintype "passive"))
      (node (ref "B8CLK_4P") (pin "5") (pinfunction "2_5") (pintype "passive"))
      (node (ref "C11") (pin "2") (pinfunction "2_2") (pintype "passive"))
      (node (ref "C11") (pin "3") (pinfunction "2_3") (pintype "passive"))
      (node (ref "C11") (pin "4") (pinfunction "2_4") (pintype "passive"))
      (node (ref "C11") (pin "5") (pinfunction "2_5") (pintype "passive"))
      (node (ref "C16") (pin "2") (pinfunction "2_2") (pintype "passive"))
      (node (ref "C16") (pin "3") (pinfunction "2_3") (pintype "passive"))
      (node (ref "C16") (pin "4") (pinfunction "2_4") (pintype "passive"))
      (node (ref "C16") (pin "5") (pinfunction "2_5") (pintype "passive"))
      (node (ref "C2") (pin "1") (pinfunction "1_1") (pintype "passive"))
      (node (ref "C4") (pin "1") (pinfunction "1_1") (pintype "passive"))
      (node (ref "C96") (pin "1") (pinfunction "1_1") (pintype "passive"))
      (node (ref "E11") (pin "2") (pinfunction "2_2") (pintype "passive"))
      (node (ref "E11") (pin "3") (pinfunction "2_3") (pintype "passive"))
      (node (ref "E11") (pin "4") (pinfunction "2_4") (pintype "passive"))
      (node (ref "E11") (pin "5") (pinfunction "2_5") (pintype "passive"))
      (node (ref "E7") (pin "2") (pinfunction "2_2") (pintype "passive"))
      (node (ref "E7") (pin "3") (pinfunction "2_3") (pintype "passive"))
      (node (ref "E7") (pin "4") (pinfunction "2_4") (pintype "passive"))
      (node (ref "E7") (pin "5") (pinfunction "2_5") (pintype "passive"))
      (node (ref "E8_T10N") (pin "2") (pinfunction "2_2") (pintype "passive"))
      (node (ref "E8_T10N") (pin "3") (pinfunction "2_3") (pintype "passive"))
      (node (ref "E8_T10N") (pin "4") (pinfunction "2_4") (pintype "passive"))
      (node (ref "E8_T10N") (pin "5") (pinfunction "2_5") (pintype "passive"))
      (node (ref "F8_T10P") (pin "2") (pinfunction "2_2") (pintype "passive"))
      (node (ref "F8_T10P") (pin "3") (pinfunction "2_3") (pintype "passive"))
      (node (ref "F8_T10P") (pin "4") (pinfunction "2_4") (pintype "passive"))
      (node (ref "F8_T10P") (pin "5") (pinfunction "2_5") (pintype "passive"))
      (node (ref "F9") (pin "2") (pinfunction "2_2") (pintype "passive"))
      (node (ref "F9") (pin "3") (pinfunction "2_3") (pintype "passive"))
      (node (ref "F9") (pin "4") (pinfunction "2_4") (pintype "passive"))
      (node (ref "F9") (pin "5") (pinfunction "2_5") (pintype "passive"))
      (node (ref "J12") (pin "3") (pinfunction "P$3_3") (pintype "bidirectional"))
      (node (ref "J13") (pin "2") (pinfunction "2_2") (pintype "passive"))
      (node (ref "J13") (pin "3") (pinfunction "2_3") (pintype "passive"))
      (node (ref "J13") (pin "4") (pinfunction "2_4") (pintype "passive"))
      (node (ref "J13") (pin "5") (pinfunction "2_5") (pintype "passive"))
      (node (ref "J17") (pin "1") (pinfunction "1_1") (pintype "bidirectional"))
      (node (ref "J18") (pin "1") (pinfunction "1_1") (pintype "bidirectional"))
      (node (ref "J22") (pin "1") (pinfunction "1_1") (pintype "bidirectional"))
      (node (ref "J23") (pin "1") (pinfunction "1_1") (pintype "bidirectional"))
      (node (ref "J24") (pin "1") (pinfunction "1_1") (pintype "bidirectional"))
      (node (ref "J25") (pin "1") (pinfunction "1_1") (pintype "bidirectional"))
      (node (ref "J32") (pin "1") (pinfunction "1_1") (pintype "bidirectional"))
      (node (ref "J33") (pin "1") (pinfunction "1_1") (pintype "bidirectional"))
      (node (ref "J34") (pin "1") (pinfunction "1_1") (pintype "bidirectional"))
      (node (ref "J35") (pin "1") (pinfunction "1_1") (pintype "bidirectional"))
      (node (ref "J36") (pin "1") (pinfunction "1_1") (pintype "bidirectional"))
      (node (ref "J37") (pin "1") (pinfunction "1_1") (pintype "bidirectional"))
      (node (ref "J38") (pin "1") (pinfunction "1_1") (pintype "bidirectional"))
      (node (ref "J39") (pin "1") (pinfunction "1_1") (pintype "bidirectional"))
      (node (ref "J4") (pin "1") (pinfunction "1_1") (pintype "bidirectional"))
      (node (ref "J40") (pin "1") (pinfunction "1_1") (pintype "bidirectional"))
      (node (ref "J41") (pin "1") (pinfunction "1_1") (pintype "bidirectional"))
      (node (ref "J42") (pin "1") (pinfunction "1_1") (pintype "bidirectional"))
      (node (ref "J43") (pin "1") (pinfunction "1_1") (pintype "bidirectional"))
      (node (ref "J5") (pin "1") (pinfunction "1_1") (pintype "bidirectional"))
      (node (ref "J6") (pin "1") (pinfunction "1_1") (pintype "bidirectional"))
      (node (ref "J7") (pin "3") (pinfunction "P$3_3") (pintype "bidirectional"))
      (node (ref "K15_R10P") (pin "2") (pinfunction "2_2") (pintype "passive"))
      (node (ref "K15_R10P") (pin "3") (pinfunction "2_3") (pintype "passive"))
      (node (ref "K15_R10P") (pin "4") (pinfunction "2_4") (pintype "passive"))
      (node (ref "K15_R10P") (pin "5") (pinfunction "2_5") (pintype "passive"))
      (node (ref "K16_R10N") (pin "2") (pinfunction "2_2") (pintype "passive"))
      (node (ref "K16_R10N") (pin "3") (pinfunction "2_3") (pintype "passive"))
      (node (ref "K16_R10N") (pin "4") (pinfunction "2_4") (pintype "passive"))
      (node (ref "K16_R10N") (pin "5") (pinfunction "2_5") (pintype "passive"))
      (node (ref "L15_R11P") (pin "2") (pinfunction "2_2") (pintype "passive"))
      (node (ref "L15_R11P") (pin "3") (pinfunction "2_3") (pintype "passive"))
      (node (ref "L15_R11P") (pin "4") (pinfunction "2_4") (pintype "passive"))
      (node (ref "L15_R11P") (pin "5") (pinfunction "2_5") (pintype "passive"))
      (node (ref "L16_R11N") (pin "2") (pinfunction "2_2") (pintype "passive"))
      (node (ref "L16_R11N") (pin "3") (pinfunction "2_3") (pintype "passive"))
      (node (ref "L16_R11N") (pin "4") (pinfunction "2_4") (pintype "passive"))
      (node (ref "L16_R11N") (pin "5") (pinfunction "2_5") (pintype "passive"))
      (node (ref "N11") (pin "2") (pinfunction "2_2") (pintype "passive"))
      (node (ref "N11") (pin "3") (pinfunction "2_3") (pintype "passive"))
      (node (ref "N11") (pin "4") (pinfunction "2_4") (pintype "passive"))
      (node (ref "N11") (pin "5") (pinfunction "2_5") (pintype "passive"))
      (node (ref "OJ41") (pin "2") (pinfunction "2_2") (pintype "bidirectional"))
      (node (ref "OJ42") (pin "2") (pinfunction "2_2") (pintype "bidirectional"))
      (node (ref "OJ43") (pin "2") (pinfunction "2_2") (pintype "bidirectional"))
      (node (ref "OJ44") (pin "2") (pinfunction "2_2") (pintype "bidirectional"))
      (node (ref "OJ45") (pin "2") (pinfunction "2_2") (pintype "bidirectional"))
      (node (ref "OJ46") (pin "2") (pinfunction "2_2") (pintype "bidirectional"))
      (node (ref "OJ47") (pin "2") (pinfunction "2_2") (pintype "bidirectional"))
      (node (ref "OJ48") (pin "2") (pinfunction "2_2") (pintype "bidirectional"))
      (node (ref "OJ57") (pin "2") (pinfunction "2_2") (pintype "bidirectional"))
      (node (ref "OJ58") (pin "2") (pinfunction "2_2") (pintype "bidirectional"))
      (node (ref "OJ59") (pin "2") (pinfunction "2_2") (pintype "bidirectional"))
      (node (ref "OJ60") (pin "2") (pinfunction "2_2") (pintype "bidirectional"))
      (node (ref "OJ61") (pin "2") (pinfunction "2_2") (pintype "bidirectional"))
      (node (ref "OJ62") (pin "2") (pinfunction "2_2") (pintype "bidirectional"))
      (node (ref "OJ63") (pin "2") (pinfunction "2_2") (pintype "bidirectional"))
      (node (ref "OJ64") (pin "2") (pinfunction "2_2") (pintype "bidirectional"))
      (node (ref "OJ73") (pin "2") (pinfunction "2_2") (pintype "bidirectional"))
      (node (ref "OJ74") (pin "2") (pinfunction "2_2") (pintype "bidirectional"))
      (node (ref "OJ75") (pin "2") (pinfunction "2_2") (pintype "bidirectional"))
      (node (ref "OJ76") (pin "2") (pinfunction "2_2") (pintype "bidirectional"))
      (node (ref "OJ77") (pin "2") (pinfunction "2_2") (pintype "bidirectional"))
      (node (ref "OJ78") (pin "2") (pinfunction "2_2") (pintype "bidirectional"))
      (node (ref "OJ79") (pin "2") (pinfunction "2_2") (pintype "bidirectional"))
      (node (ref "OJ80") (pin "2") (pinfunction "2_2") (pintype "bidirectional"))
      (node (ref "P11") (pin "2") (pinfunction "2_2") (pintype "passive"))
      (node (ref "P11") (pin "3") (pinfunction "2_3") (pintype "passive"))
      (node (ref "P11") (pin "4") (pinfunction "2_4") (pintype "passive"))
      (node (ref "P11") (pin "5") (pinfunction "2_5") (pintype "passive"))
      (node (ref "P15") (pin "2") (pinfunction "2_2") (pintype "passive"))
      (node (ref "P15") (pin "3") (pinfunction "2_3") (pintype "passive"))
      (node (ref "P15") (pin "4") (pinfunction "2_4") (pintype "passive"))
      (node (ref "P15") (pin "5") (pinfunction "2_5") (pintype "passive"))
      (node (ref "P16_R15N") (pin "2") (pinfunction "2_2") (pintype "passive"))
      (node (ref "P16_R15N") (pin "3") (pinfunction "2_3") (pintype "passive"))
      (node (ref "P16_R15N") (pin "4") (pinfunction "2_4") (pintype "passive"))
      (node (ref "P16_R15N") (pin "5") (pinfunction "2_5") (pintype "passive"))
      (node (ref "P9") (pin "2") (pinfunction "2_2") (pintype "passive"))
      (node (ref "P9") (pin "3") (pinfunction "2_3") (pintype "passive"))
      (node (ref "P9") (pin "4") (pinfunction "2_4") (pintype "passive"))
      (node (ref "P9") (pin "5") (pinfunction "2_5") (pintype "passive"))
      (node (ref "R11") (pin "P$1") (pinfunction "1_P$1") (pintype "passive"))
      (node (ref "R13_B20P") (pin "2") (pinfunction "2_2") (pintype "passive"))
      (node (ref "R13_B20P") (pin "3") (pinfunction "2_3") (pintype "passive"))
      (node (ref "R13_B20P") (pin "4") (pinfunction "2_4") (pintype "passive"))
      (node (ref "R13_B20P") (pin "5") (pinfunction "2_5") (pintype "passive"))
      (node (ref "R161") (pin "P$1") (pinfunction "1_P$1") (pintype "passive"))
      (node (ref "R16_R15P") (pin "2") (pinfunction "2_2") (pintype "passive"))
      (node (ref "R16_R15P") (pin "3") (pinfunction "2_3") (pintype "passive"))
      (node (ref "R16_R15P") (pin "4") (pinfunction "2_4") (pintype "passive"))
      (node (ref "R16_R15P") (pin "5") (pinfunction "2_5") (pintype "passive"))
      (node (ref "R20") (pin "P$1") (pinfunction "1_P$1") (pintype "passive"))
      (node (ref "R21") (pin "P$1") (pinfunction "1_P$1") (pintype "passive"))
      (node (ref "R22") (pin "P$1") (pinfunction "1_P$1") (pintype "passive"))
      (node (ref "R23") (pin "P$1") (pinfunction "1_P$1") (pintype "passive"))
      (node (ref "R25") (pin "P$1") (pinfunction "1_P$1") (pintype "passive"))
      (node (ref "R28") (pin "P$1") (pinfunction "1_P$1") (pintype "passive"))
      (node (ref "R30") (pin "P$1") (pinfunction "1_P$1") (pintype "passive"))
      (node (ref "R31") (pin "P$1") (pinfunction "1_P$1") (pintype "passive"))
      (node (ref "R32") (pin "P$1") (pinfunction "1_P$1") (pintype "passive"))
      (node (ref "R33") (pin "P$1") (pinfunction "1_P$1") (pintype "passive"))
      (node (ref "R35") (pin "P$1") (pinfunction "1_P$1") (pintype "passive"))
      (node (ref "R39") (pin "P$1") (pinfunction "1_P$1") (pintype "passive"))
      (node (ref "R4") (pin "P$1") (pinfunction "1_P$1") (pintype "passive"))
      (node (ref "R40") (pin "P$1") (pinfunction "1_P$1") (pintype "passive"))
      (node (ref "R41") (pin "P$1") (pinfunction "1_P$1") (pintype "passive"))
      (node (ref "R43") (pin "P$1") (pinfunction "1_P$1") (pintype "passive"))
      (node (ref "R5") (pin "P$1") (pinfunction "1_P$1") (pintype "passive"))
      (node (ref "R6") (pin "P$1") (pinfunction "1_P$1") (pintype "passive"))
      (node (ref "R8") (pin "2") (pinfunction "2_2") (pintype "passive"))
      (node (ref "R9") (pin "P$1") (pinfunction "1_P$1") (pintype "passive"))
      (node (ref "R9CLK_7P") (pin "2") (pinfunction "2_2") (pintype "passive"))
      (node (ref "R9CLK_7P") (pin "3") (pinfunction "2_3") (pintype "passive"))
      (node (ref "R9CLK_7P") (pin "4") (pinfunction "2_4") (pintype "passive"))
      (node (ref "R9CLK_7P") (pin "5") (pinfunction "2_5") (pintype "passive"))
      (node (ref "SV1") (pin "12") (pinfunction "12_12") (pintype "passive"))
      (node (ref "SV1") (pin "30") (pinfunction "30_30") (pintype "passive"))
      (node (ref "SV2") (pin "12") (pinfunction "12_12") (pintype "passive"))
      (node (ref "SV2") (pin "30") (pinfunction "30_30") (pintype "passive"))
      (node (ref "T13_B20N") (pin "2") (pinfunction "2_2") (pintype "passive"))
      (node (ref "T13_B20N") (pin "3") (pinfunction "2_3") (pintype "passive"))
      (node (ref "T13_B20N") (pin "4") (pinfunction "2_4") (pintype "passive"))
      (node (ref "T13_B20N") (pin "5") (pinfunction "2_5") (pintype "passive"))
      (node (ref "T14_B23P") (pin "2") (pinfunction "2_2") (pintype "passive"))
      (node (ref "T14_B23P") (pin "3") (pinfunction "2_3") (pintype "passive"))
      (node (ref "T14_B23P") (pin "4") (pinfunction "2_4") (pintype "passive"))
      (node (ref "T14_B23P") (pin "5") (pinfunction "2_5") (pintype "passive"))
      (node (ref "T15_B23N") (pin "2") (pinfunction "2_2") (pintype "passive"))
      (node (ref "T15_B23N") (pin "3") (pinfunction "2_3") (pintype "passive"))
      (node (ref "T15_B23N") (pin "4") (pinfunction "2_4") (pintype "passive"))
      (node (ref "T15_B23N") (pin "5") (pinfunction "2_5") (pintype "passive"))
      (node (ref "T9CLK_7N") (pin "2") (pinfunction "2_2") (pintype "passive"))
      (node (ref "T9CLK_7N") (pin "3") (pinfunction "2_3") (pintype "passive"))
      (node (ref "T9CLK_7N") (pin "4") (pinfunction "2_4") (pintype "passive"))
      (node (ref "T9CLK_7N") (pin "5") (pinfunction "2_5") (pintype "passive"))
      (node (ref "VSLUE5") (pin "10") (pinfunction "GND_10") (pintype "power_in"))
      (node (ref "VSLUE7") (pin "10") (pinfunction "GND_10") (pintype "power_in"))
      (node (ref "VSLUE9") (pin "10") (pinfunction "GND_10") (pintype "power_in"))
    )
    (net (code "4") (name "/GPIO_00_D3") (class "Default")
      (node (ref "SV1") (pin "2") (pinfunction "2_2") (pintype "passive"))
    )
    (net (code "5") (name "/GPIO_0_IN0_A8CLK") (class "Default")
      (node (ref "A8CLK_4N") (pin "1") (pinfunction "1_1") (pintype "passive"))
      (node (ref "J24") (pin "2") (pinfunction "2_2") (pintype "bidirectional"))
      (node (ref "R23") (pin "P$2") (pinfunction "2_P$2") (pintype "passive"))
      (node (ref "SV1") (pin "1") (pinfunction "1_1") (pintype "passive"))
    )
    (net (code "6") (name "/GPIO_0_IN1_B8CLK") (class "Default")
      (node (ref "B8CLK_4P") (pin "1") (pinfunction "1_1") (pintype "passive"))
      (node (ref "J23") (pin "2") (pinfunction "2_2") (pintype "bidirectional"))
      (node (ref "R22") (pin "P$2") (pinfunction "2_P$2") (pintype "passive"))
      (node (ref "SV1") (pin "3") (pinfunction "3_3") (pintype "passive"))
    )
    (net (code "7") (name "/GPIO_01_C3") (class "Default")
      (node (ref "SV1") (pin "4") (pinfunction "4_4") (pintype "passive"))
    )
    (net (code "8") (name "/GPIO_1_IN0_T9CLK") (class "Default")
      (node (ref "J6") (pin "2") (pinfunction "2_2") (pintype "bidirectional"))
      (node (ref "R6") (pin "P$2") (pinfunction "2_P$2") (pintype "passive"))
      (node (ref "SV2") (pin "1") (pinfunction "1_1") (pintype "passive"))
      (node (ref "T9CLK_7N") (pin "1") (pinfunction "1_1") (pintype "passive"))
    )
    (net (code "9") (name "/GPIO_1_IN1_R9CLK") (class "Default")
      (node (ref "J5") (pin "2") (pinfunction "2_2") (pintype "bidirectional"))
      (node (ref "R5") (pin "P$2") (pinfunction "2_P$2") (pintype "passive"))
      (node (ref "R9CLK_7P") (pin "1") (pinfunction "1_1") (pintype "passive"))
      (node (ref "SV2") (pin "3") (pinfunction "3_3") (pintype "passive"))
    )
    (net (code "10") (name "/GPIO_02_A2") (class "Default")
      (node (ref "A2_T2N") (pin "1") (pinfunction "1_1") (pintype "passive"))
      (node (ref "J22") (pin "2") (pinfunction "2_2") (pintype "bidirectional"))
      (node (ref "R20") (pin "P$2") (pinfunction "2_P$2") (pintype "passive"))
      (node (ref "SV1") (pin "5") (pinfunction "5_5") (pintype "passive"))
    )
    (net (code "11") (name "/GPIO_03_A3") (class "Default")
      (node (ref "A3_T2P") (pin "1") (pinfunction "1_1") (pintype "passive"))
      (node (ref "J25") (pin "2") (pinfunction "2_2") (pintype "bidirectional"))
      (node (ref "R25") (pin "P$2") (pinfunction "2_P$2") (pintype "passive"))
      (node (ref "SV1") (pin "6") (pinfunction "6_6") (pintype "passive"))
    )
    (net (code "12") (name "/GPIO_04_B3") (class "Default")
      (node (ref "SV1") (pin "7") (pinfunction "7_7") (pintype "passive"))
    )
    (net (code "13") (name "/GPIO_05_B4") (class "Default")
      (node (ref "SV1") (pin "8") (pinfunction "8_8") (pintype "passive"))
    )
    (net (code "14") (name "/GPIO_06_A4") (class "Default")
      (node (ref "SV1") (pin "9") (pinfunction "9_9") (pintype "passive"))
    )
    (net (code "15") (name "/GPIO_07_B5") (class "Default")
      (node (ref "SV1") (pin "10") (pinfunction "10_10") (pintype "passive"))
    )
    (net (code "16") (name "/GPIO_08_A5") (class "Default")
      (node (ref "SV1") (pin "13") (pinfunction "13_13") (pintype "passive"))
    )
    (net (code "17") (name "/GPIO_09_D5") (class "Default")
      (node (ref "SV1") (pin "14") (pinfunction "14_14") (pintype "passive"))
    )
    (net (code "18") (name "/GPIO_010_B6") (class "Default")
      (node (ref "OJ47") (pin "1") (pinfunction "1_1") (pintype "bidirectional"))
      (node (ref "SV1") (pin "15") (pinfunction "15_15") (pintype "passive"))
      (node (ref "VSLUE5") (pin "2") (pinfunction "1A1_2") (pintype "input"))
      (node (ref "VSLUE5") (pin "4") (pinfunction "1A2_4") (pintype "input"))
    )
    (net (code "19") (name "/GPIO_10_F13") (class "Default")
      (node (ref "J3") (pin "2") (pinfunction "P$2_2") (pintype "bidirectional"))
      (node (ref "SV2") (pin "2") (pinfunction "2_2") (pintype "passive"))
    )
    (net (code "20") (name "/GPIO_011_A6") (class "Default")
      (node (ref "OJ48") (pin "1") (pinfunction "1_1") (pintype "bidirectional"))
      (node (ref "SV1") (pin "16") (pinfunction "16_16") (pintype "passive"))
      (node (ref "VSLUE5") (pin "6") (pinfunction "1A3_6") (pintype "input"))
      (node (ref "VSLUE5") (pin "8") (pinfunction "1A4_8") (pintype "input"))
    )
    (net (code "21") (name "/GPIO_11_T15") (class "Default")
      (node (ref "J40") (pin "2") (pinfunction "2_2") (pintype "bidirectional"))
      (node (ref "R39") (pin "P$2") (pinfunction "2_P$2") (pintype "passive"))
      (node (ref "SV2") (pin "4") (pinfunction "4_4") (pintype "passive"))
      (node (ref "T15_B23N") (pin "1") (pinfunction "1_1") (pintype "passive"))
    )
    (net (code "22") (name "/GPIO_012_B7") (class "Default")
      (node (ref "SV1") (pin "17") (pinfunction "17_17") (pintype "passive"))
    )
    (net (code "23") (name "/GPIO_12_T14") (class "Default")
      (node (ref "J4") (pin "2") (pinfunction "2_2") (pintype "bidirectional"))
      (node (ref "R4") (pin "P$2") (pinfunction "2_P$2") (pintype "passive"))
      (node (ref "SV2") (pin "5") (pinfunction "5_5") (pintype "passive"))
      (node (ref "T14_B23P") (pin "1") (pinfunction "1_1") (pintype "passive"))
    )
    (net (code "24") (name "/GPIO_013_D6") (class "Default")
      (node (ref "SV1") (pin "18") (pinfunction "18_18") (pintype "passive"))
    )
    (net (code "25") (name "/GPIO_13_T13") (class "Default")
      (node (ref "J38") (pin "2") (pinfunction "2_2") (pintype "bidirectional"))
      (node (ref "R32") (pin "P$2") (pinfunction "2_P$2") (pintype "passive"))
      (node (ref "SV2") (pin "6") (pinfunction "6_6") (pintype "passive"))
      (node (ref "T13_B20N") (pin "1") (pinfunction "1_1") (pintype "passive"))
    )
    (net (code "26") (name "/GPIO_014_A7") (class "Default")
      (node (ref "A7_T9N") (pin "1") (pinfunction "1_1") (pintype "passive"))
      (node (ref "J35") (pin "2") (pinfunction "2_2") (pintype "bidirectional"))
      (node (ref "R33") (pin "P$2") (pinfunction "2_P$2") (pintype "passive"))
      (node (ref "SV1") (pin "19") (pinfunction "19_19") (pintype "passive"))
    )
    (net (code "27") (name "/GPIO_14_R13") (class "Default")
      (node (ref "J17") (pin "2") (pinfunction "2_2") (pintype "bidirectional"))
      (node (ref "R13_B20P") (pin "1") (pinfunction "1_1") (pintype "passive"))
      (node (ref "R161") (pin "P$2") (pinfunction "2_P$2") (pintype "passive"))
      (node (ref "SV2") (pin "7") (pinfunction "7_7") (pintype "passive"))
    )
    (net (code "28") (name "/GPIO_015_C6") (class "Default")
      (node (ref "SV1") (pin "20") (pinfunction "20_20") (pintype "passive"))
    )
    (net (code "29") (name "/GPIO_15_T12") (class "Default")
      (node (ref "SV2") (pin "8") (pinfunction "8_8") (pintype "passive"))
    )
    (net (code "30") (name "/GPIO_016_C8") (class "Default")
      (node (ref "SV1") (pin "21") (pinfunction "21_21") (pintype "passive"))
    )
    (net (code "31") (name "/GPIO_16_R12") (class "Default")
      (node (ref "SV2") (pin "9") (pinfunction "9_9") (pintype "passive"))
    )
    (net (code "32") (name "/GPIO_017_E6") (class "Default")
      (node (ref "SV1") (pin "22") (pinfunction "22_22") (pintype "passive"))
    )
    (net (code "33") (name "/GPIO_17_T11") (class "Default")
      (node (ref "J3") (pin "3") (pinfunction "P$3_3") (pintype "bidirectional"))
      (node (ref "SV2") (pin "10") (pinfunction "10_10") (pintype "passive"))
    )
    (net (code "34") (name "/GPIO_018_E7") (class "Default")
      (node (ref "OJ64") (pin "1") (pinfunction "1_1") (pintype "bidirectional"))
      (node (ref "SV1") (pin "23") (pinfunction "23_23") (pintype "passive"))
      (node (ref "VSLUE7") (pin "6") (pinfunction "1A3_6") (pintype "input"))
      (node (ref "VSLUE7") (pin "8") (pinfunction "1A4_8") (pintype "input"))
    )
    (net (code "35") (name "/GPIO_18_T10") (class "Default")
      (node (ref "SV2") (pin "13") (pinfunction "13_13") (pintype "passive"))
    )
    (net (code "36") (name "/GPIO_019_D8") (class "Default")
      (node (ref "SV1") (pin "24") (pinfunction "24_24") (pintype "passive"))
    )
    (net (code "37") (name "/GPIO_19_R11") (class "Default")
      (node (ref "J3") (pin "1") (pinfunction "P$1_1") (pintype "bidirectional"))
      (node (ref "SV2") (pin "14") (pinfunction "14_14") (pintype "passive"))
    )
    (net (code "38") (name "/GPIO_020_E8") (class "Default")
      (node (ref "E8_T10N") (pin "1") (pinfunction "1_1") (pintype "passive"))
      (node (ref "J41") (pin "2") (pinfunction "2_2") (pintype "bidirectional"))
      (node (ref "R40") (pin "P$2") (pinfunction "2_P$2") (pintype "passive"))
      (node (ref "SV1") (pin "25") (pinfunction "25_25") (pintype "passive"))
    )
    (net (code "39") (name "/GPIO_021_F8") (class "Default")
      (node (ref "F8_T10P") (pin "1") (pinfunction "1_1") (pintype "passive"))
      (node (ref "J18") (pin "2") (pinfunction "2_2") (pintype "bidirectional"))
      (node (ref "R21") (pin "P$2") (pinfunction "2_P$2") (pintype "passive"))
      (node (ref "SV1") (pin "26") (pinfunction "26_26") (pintype "passive"))
    )
    (net (code "40") (name "/GPIO_022_F9") (class "Default")
      (node (ref "OJ62") (pin "1") (pinfunction "1_1") (pintype "bidirectional"))
      (node (ref "SV1") (pin "27") (pinfunction "27_27") (pintype "passive"))
      (node (ref "VSLUE7") (pin "11") (pinfunction "2A1_11") (pintype "input"))
      (node (ref "VSLUE7") (pin "13") (pinfunction "2A2_13") (pintype "input"))
    )
    (net (code "41") (name "/GPIO_23_C16") (class "Default")
      (node (ref "OJ63") (pin "1") (pinfunction "1_1") (pintype "bidirectional"))
      (node (ref "VSLUE7") (pin "2") (pinfunction "1A1_2") (pintype "input"))
      (node (ref "VSLUE7") (pin "4") (pinfunction "1A2_4") (pintype "input"))
    )
    (net (code "42") (name "/GPIO_023_E9") (class "Default")
      (node (ref "SV1") (pin "28") (pinfunction "28_28") (pintype "passive"))
    )
    (net (code "43") (name "/GPIO_024_C9") (class "Default")
      (node (ref "SV1") (pin "31") (pinfunction "31_31") (pintype "passive"))
    )
    (net (code "44") (name "/GPIO_025_D9") (class "Default")
      (node (ref "SV1") (pin "32") (pinfunction "32_32") (pintype "passive"))
    )
    (net (code "45") (name "/GPIO_026_E11") (class "Default")
      (node (ref "OJ79") (pin "1") (pinfunction "1_1") (pintype "bidirectional"))
      (node (ref "SV1") (pin "33") (pinfunction "33_33") (pintype "passive"))
      (node (ref "VSLUE9") (pin "2") (pinfunction "1A1_2") (pintype "input"))
      (node (ref "VSLUE9") (pin "4") (pinfunction "1A2_4") (pintype "input"))
    )
    (net (code "46") (name "/GPIO_027_E10") (class "Default")
      (node (ref "SV1") (pin "34") (pinfunction "34_34") (pintype "passive"))
    )
    (net (code "47") (name "/GPIO_028_C11") (class "Default")
      (node (ref "OJ78") (pin "1") (pinfunction "1_1") (pintype "bidirectional"))
      (node (ref "SV1") (pin "35") (pinfunction "35_35") (pintype "passive"))
      (node (ref "VSLUE9") (pin "11") (pinfunction "2A1_11") (pintype "input"))
      (node (ref "VSLUE9") (pin "13") (pinfunction "2A2_13") (pintype "input"))
    )
    (net (code "48") (name "/GPIO_029_B11") (class "Default")
      (node (ref "SV1") (pin "36") (pinfunction "36_36") (pintype "passive"))
    )
    (net (code "49") (name "/GPIO_030_A12") (class "Default")
      (node (ref "A12_T21N") (pin "1") (pinfunction "1_1") (pintype "passive"))
      (node (ref "J36") (pin "2") (pinfunction "2_2") (pintype "bidirectional"))
      (node (ref "R9") (pin "P$2") (pinfunction "2_P$2") (pintype "passive"))
      (node (ref "SV1") (pin "37") (pinfunction "37_37") (pintype "passive"))
    )
    (net (code "50") (name "/GPIO_031_D11") (class "Default")
      (node (ref "SV1") (pin "38") (pinfunction "38_38") (pintype "passive"))
    )
    (net (code "51") (name "/GPIO_032_D12") (class "Default")
      (node (ref "SV1") (pin "39") (pinfunction "39_39") (pintype "passive"))
    )
    (net (code "52") (name "/GPIO_033_B12") (class "Default")
      (node (ref "B12_T21P") (pin "1") (pinfunction "1_1") (pintype "passive"))
      (node (ref "J37") (pin "2") (pinfunction "2_2") (pintype "bidirectional"))
      (node (ref "R11") (pin "P$2") (pinfunction "2_P$2") (pintype "passive"))
      (node (ref "SV1") (pin "40") (pinfunction "40_40") (pintype "passive"))
    )
    (net (code "53") (name "/GPIO_110_P11") (class "Default")
      (node (ref "OJ80") (pin "1") (pinfunction "1_1") (pintype "bidirectional"))
      (node (ref "SV2") (pin "15") (pinfunction "15_15") (pintype "passive"))
      (node (ref "VSLUE9") (pin "6") (pinfunction "1A3_6") (pintype "input"))
      (node (ref "VSLUE9") (pin "8") (pinfunction "1A4_8") (pintype "input"))
    )
    (net (code "54") (name "/GPIO_111_R10") (class "Default")
      (node (ref "SV2") (pin "16") (pinfunction "16_16") (pintype "passive"))
    )
    (net (code "55") (name "/GPIO_112_N12") (class "Default")
      (node (ref "SV2") (pin "17") (pinfunction "17_17") (pintype "passive"))
    )
    (net (code "56") (name "/GPIO_113_P9") (class "Default")
      (node (ref "OJ45") (pin "1") (pinfunction "1_1") (pintype "bidirectional"))
      (node (ref "SV2") (pin "18") (pinfunction "18_18") (pintype "passive"))
      (node (ref "VSLUE5") (pin "15") (pinfunction "2A3_15") (pintype "input"))
      (node (ref "VSLUE5") (pin "17") (pinfunction "2A4_17") (pintype "input"))
    )
    (net (code "57") (name "/GPIO_114_N9") (class "Default")
      (node (ref "J3") (pin "4") (pinfunction "P$4_4") (pintype "bidirectional"))
      (node (ref "LED1") (pin "A") (pinfunction "A_A") (pintype "passive"))
      (node (ref "R17") (pin "P$2") (pinfunction "2_P$2") (pintype "passive"))
      (node (ref "SV2") (pin "19") (pinfunction "19_19") (pintype "passive"))
      (node (ref "VSLUE5") (pin "1") (pinfunction "~{1OE}_1") (pintype "input"))
      (node (ref "VSLUE5") (pin "19") (pinfunction "~{2OE}_19") (pintype "input"))
      (node (ref "VSLUE7") (pin "1") (pinfunction "~{1OE}_1") (pintype "input"))
      (node (ref "VSLUE7") (pin "19") (pinfunction "~{2OE}_19") (pintype "input"))
      (node (ref "VSLUE9") (pin "1") (pinfunction "~{1OE}_1") (pintype "input"))
      (node (ref "VSLUE9") (pin "19") (pinfunction "~{2OE}_19") (pintype "input"))
    )
    (net (code "58") (name "/GPIO_115_N11") (class "Default")
      (node (ref "OJ46") (pin "1") (pinfunction "1_1") (pintype "bidirectional"))
      (node (ref "SV2") (pin "20") (pinfunction "20_20") (pintype "passive"))
      (node (ref "VSLUE5") (pin "11") (pinfunction "2A1_11") (pintype "input"))
      (node (ref "VSLUE5") (pin "13") (pinfunction "2A2_13") (pintype "input"))
    )
    (net (code "59") (name "/GPIO_116_L16") (class "Default")
      (node (ref "J32") (pin "2") (pinfunction "2_2") (pintype "bidirectional"))
      (node (ref "L16_R11N") (pin "1") (pinfunction "1_1") (pintype "passive"))
      (node (ref "R28") (pin "P$2") (pinfunction "2_P$2") (pintype "passive"))
      (node (ref "SV2") (pin "21") (pinfunction "21_21") (pintype "passive"))
    )
    (net (code "60") (name "/GPIO_117_K16") (class "Default")
      (node (ref "J33") (pin "2") (pinfunction "2_2") (pintype "bidirectional"))
      (node (ref "K16_R10N") (pin "1") (pinfunction "1_1") (pintype "passive"))
      (node (ref "R30") (pin "P$2") (pinfunction "2_P$2") (pintype "passive"))
      (node (ref "SV2") (pin "22") (pinfunction "22_22") (pintype "passive"))
    )
    (net (code "61") (name "/GPIO_118_R16") (class "Default")
      (node (ref "J34") (pin "2") (pinfunction "2_2") (pintype "bidirectional"))
      (node (ref "R16_R15P") (pin "1") (pinfunction "1_1") (pintype "passive"))
      (node (ref "R31") (pin "P$2") (pinfunction "2_P$2") (pintype "passive"))
      (node (ref "SV2") (pin "23") (pinfunction "23_23") (pintype "passive"))
    )
    (net (code "62") (name "/GPIO_119_L15") (class "Default")
      (node (ref "J43") (pin "2") (pinfunction "2_2") (pintype "bidirectional"))
      (node (ref "L15_R11P") (pin "1") (pinfunction "1_1") (pintype "passive"))
      (node (ref "R43") (pin "P$2") (pinfunction "2_P$2") (pintype "passive"))
      (node (ref "SV2") (pin "24") (pinfunction "24_24") (pintype "passive"))
    )
    (net (code "63") (name "/GPIO_120_P15") (class "Default")
      (node (ref "OJ61") (pin "1") (pinfunction "1_1") (pintype "bidirectional"))
      (node (ref "SV2") (pin "25") (pinfunction "25_25") (pintype "passive"))
      (node (ref "VSLUE7") (pin "15") (pinfunction "2A3_15") (pintype "input"))
      (node (ref "VSLUE7") (pin "17") (pinfunction "2A4_17") (pintype "input"))
    )
    (net (code "64") (name "/GPIO_121_P16") (class "Default")
      (node (ref "J42") (pin "2") (pinfunction "2_2") (pintype "bidirectional"))
      (node (ref "P16_R15N") (pin "1") (pinfunction "1_1") (pintype "passive"))
      (node (ref "R41") (pin "P$2") (pinfunction "2_P$2") (pintype "passive"))
      (node (ref "SV2") (pin "26") (pinfunction "26_26") (pintype "passive"))
    )
    (net (code "65") (name "/GPIO_122_R14") (class "Default")
      (node (ref "SV2") (pin "27") (pinfunction "27_27") (pintype "passive"))
    )
    (net (code "66") (name "/GPIO_123_N16") (class "Default")
      (node (ref "SV2") (pin "28") (pinfunction "28_28") (pintype "passive"))
    )
    (net (code "67") (name "/GPIO_124_N15") (class "Default")
      (node (ref "SV2") (pin "31") (pinfunction "31_31") (pintype "passive"))
    )
    (net (code "68") (name "/GPIO_125_P14") (class "Default")
      (node (ref "SV2") (pin "32") (pinfunction "32_32") (pintype "passive"))
    )
    (net (code "69") (name "/GPIO_126_L14") (class "Default")
      (node (ref "J7") (pin "2") (pinfunction "P$2_2") (pintype "bidirectional"))
      (node (ref "SV2") (pin "33") (pinfunction "33_33") (pintype "passive"))
    )
    (net (code "70") (name "/GPIO_127_N14") (class "Default")
      (node (ref "SV2") (pin "34") (pinfunction "34_34") (pintype "passive"))
    )
    (net (code "71") (name "/GPIO_128_M10") (class "Default")
      (node (ref "J12") (pin "2") (pinfunction "P$2_2") (pintype "bidirectional"))
      (node (ref "SV2") (pin "35") (pinfunction "35_35") (pintype "passive"))
    )
    (net (code "72") (name "/GPIO_129_L13") (class "Default")
      (node (ref "J7") (pin "1") (pinfunction "P$1_1") (pintype "bidirectional"))
      (node (ref "SV2") (pin "36") (pinfunction "36_36") (pintype "passive"))
    )
    (net (code "73") (name "/GPIO_130_J16") (class "Default")
      (node (ref "J12") (pin "1") (pinfunction "P$1_1") (pintype "bidirectional"))
      (node (ref "SV2") (pin "37") (pinfunction "37_37") (pintype "passive"))
    )
    (net (code "74") (name "/GPIO_131_K15") (class "Default")
      (node (ref "J39") (pin "2") (pinfunction "2_2") (pintype "bidirectional"))
      (node (ref "K15_R10P") (pin "1") (pinfunction "1_1") (pintype "passive"))
      (node (ref "R35") (pin "P$2") (pinfunction "2_P$2") (pintype "passive"))
      (node (ref "SV2") (pin "38") (pinfunction "38_38") (pintype "passive"))
    )
    (net (code "75") (name "/GPIO_132_J13") (class "Default")
      (node (ref "OJ77") (pin "1") (pinfunction "1_1") (pintype "bidirectional"))
      (node (ref "SV2") (pin "39") (pinfunction "39_39") (pintype "passive"))
      (node (ref "VSLUE9") (pin "15") (pinfunction "2A3_15") (pintype "input"))
      (node (ref "VSLUE9") (pin "17") (pinfunction "2A4_17") (pintype "input"))
    )
    (net (code "76") (name "/GPIO_133_J14") (class "Default")
      (node (ref "SV2") (pin "40") (pinfunction "40_40") (pintype "passive"))
    )
    (net (code "77") (name "Net-(LED1-PadC)") (class "Default")
      (node (ref "LED1") (pin "C") (pinfunction "C_C") (pintype "passive"))
      (node (ref "R8") (pin "1") (pinfunction "1_1") (pintype "passive"))
    )
    (net (code "78") (name "Net-(VSLUE5-1Y1)") (class "Default")
      (node (ref "B6") (pin "1") (pinfunction "1_1") (pintype "passive"))
      (node (ref "OJ44") (pin "1") (pinfunction "1_1") (pintype "bidirectional"))
      (node (ref "VSLUE5") (pin "16") (pinfunction "1Y2_16") (pintype "output"))
      (node (ref "VSLUE5") (pin "18") (pinfunction "1Y1_18") (pintype "output"))
    )
    (net (code "79") (name "Net-(VSLUE5-1Y3)") (class "Default")
      (node (ref "A6") (pin "1") (pinfunction "1_1") (pintype "passive"))
      (node (ref "OJ43") (pin "1") (pinfunction "1_1") (pintype "bidirectional"))
      (node (ref "VSLUE5") (pin "12") (pinfunction "1Y4_12") (pintype "output"))
      (node (ref "VSLUE5") (pin "14") (pinfunction "1Y3_14") (pintype "output"))
    )
    (net (code "80") (name "Net-(VSLUE5-2Y1)") (class "Default")
      (node (ref "N11") (pin "1") (pinfunction "1_1") (pintype "passive"))
      (node (ref "OJ42") (pin "1") (pinfunction "1_1") (pintype "bidirectional"))
      (node (ref "VSLUE5") (pin "7") (pinfunction "2Y2_7") (pintype "output"))
      (node (ref "VSLUE5") (pin "9") (pinfunction "2Y1_9") (pintype "output"))
    )
    (net (code "81") (name "Net-(VSLUE5-2Y3)") (class "Default")
      (node (ref "OJ41") (pin "1") (pinfunction "1_1") (pintype "bidirectional"))
      (node (ref "P9") (pin "1") (pinfunction "1_1") (pintype "passive"))
      (node (ref "VSLUE5") (pin "3") (pinfunction "2Y4_3") (pintype "output"))
      (node (ref "VSLUE5") (pin "5") (pinfunction "2Y3_5") (pintype "output"))
    )
    (net (code "82") (name "Net-(VSLUE7-1Y1)") (class "Default")
      (node (ref "C16") (pin "1") (pinfunction "1_1") (pintype "passive"))
      (node (ref "OJ60") (pin "1") (pinfunction "1_1") (pintype "bidirectional"))
      (node (ref "VSLUE7") (pin "16") (pinfunction "1Y2_16") (pintype "output"))
      (node (ref "VSLUE7") (pin "18") (pinfunction "1Y1_18") (pintype "output"))
    )
    (net (code "83") (name "Net-(VSLUE7-1Y3)") (class "Default")
      (node (ref "E7") (pin "1") (pinfunction "1_1") (pintype "passive"))
      (node (ref "OJ59") (pin "1") (pinfunction "1_1") (pintype "bidirectional"))
      (node (ref "VSLUE7") (pin "12") (pinfunction "1Y4_12") (pintype "output"))
      (node (ref "VSLUE7") (pin "14") (pinfunction "1Y3_14") (pintype "output"))
    )
    (net (code "84") (name "Net-(VSLUE7-2Y1)") (class "Default")
      (node (ref "F9") (pin "1") (pinfunction "1_1") (pintype "passive"))
      (node (ref "OJ58") (pin "1") (pinfunction "1_1") (pintype "bidirectional"))
      (node (ref "VSLUE7") (pin "7") (pinfunction "2Y2_7") (pintype "output"))
      (node (ref "VSLUE7") (pin "9") (pinfunction "2Y1_9") (pintype "output"))
    )
    (net (code "85") (name "Net-(VSLUE7-2Y3)") (class "Default")
      (node (ref "OJ57") (pin "1") (pinfunction "1_1") (pintype "bidirectional"))
      (node (ref "P15") (pin "1") (pinfunction "1_1") (pintype "passive"))
      (node (ref "VSLUE7") (pin "3") (pinfunction "2Y4_3") (pintype "output"))
      (node (ref "VSLUE7") (pin "5") (pinfunction "2Y3_5") (pintype "output"))
    )
    (net (code "86") (name "Net-(VSLUE9-1Y1)") (class "Default")
      (node (ref "E11") (pin "1") (pinfunction "1_1") (pintype "passive"))
      (node (ref "OJ76") (pin "1") (pinfunction "1_1") (pintype "bidirectional"))
      (node (ref "VSLUE9") (pin "16") (pinfunction "1Y2_16") (pintype "output"))
      (node (ref "VSLUE9") (pin "18") (pinfunction "1Y1_18") (pintype "output"))
    )
    (net (code "87") (name "Net-(VSLUE9-1Y3)") (class "Default")
      (node (ref "OJ75") (pin "1") (pinfunction "1_1") (pintype "bidirectional"))
      (node (ref "P11") (pin "1") (pinfunction "1_1") (pintype "passive"))
      (node (ref "VSLUE9") (pin "12") (pinfunction "1Y4_12") (pintype "output"))
      (node (ref "VSLUE9") (pin "14") (pinfunction "1Y3_14") (pintype "output"))
    )
    (net (code "88") (name "Net-(VSLUE9-2Y1)") (class "Default")
      (node (ref "C11") (pin "1") (pinfunction "1_1") (pintype "passive"))
      (node (ref "OJ74") (pin "1") (pinfunction "1_1") (pintype "bidirectional"))
      (node (ref "VSLUE9") (pin "7") (pinfunction "2Y2_7") (pintype "output"))
      (node (ref "VSLUE9") (pin "9") (pinfunction "2Y1_9") (pintype "output"))
    )
    (net (code "89") (name "Net-(VSLUE9-2Y3)") (class "Default")
      (node (ref "J13") (pin "1") (pinfunction "1_1") (pintype "passive"))
      (node (ref "OJ73") (pin "1") (pinfunction "1_1") (pintype "bidirectional"))
      (node (ref "VSLUE9") (pin "3") (pinfunction "2Y4_3") (pintype "output"))
      (node (ref "VSLUE9") (pin "5") (pinfunction "2Y3_5") (pintype "output"))
    )
    (net (code "90") (name "unconnected-(J2-Pad1)") (class "Default")
      (node (ref "J2") (pin "1") (pinfunction "1_1") (pintype "passive"))
    )
    (net (code "91") (name "unconnected-(J2-Pad2)") (class "Default")
      (node (ref "J2") (pin "2") (pinfunction "2_2") (pintype "passive"))
    )
    (net (code "92") (name "unconnected-(J2-Pad3)") (class "Default")
      (node (ref "J2") (pin "3") (pinfunction "3_3") (pintype "passive"))
    )
    (net (code "93") (name "unconnected-(J2-Pad4)") (class "Default")
      (node (ref "J2") (pin "4") (pinfunction "4_4") (pintype "passive"))
    )
    (net (code "94") (name "unconnected-(J2-Pad5)") (class "Default")
      (node (ref "J2") (pin "5") (pinfunction "5_5") (pintype "passive"))
    )
    (net (code "95") (name "unconnected-(J2-Pad6)") (class "Default")
      (node (ref "J2") (pin "6") (pinfunction "6_6") (pintype "passive"))
    )
    (net (code "96") (name "unconnected-(J2-Pad7)") (class "Default")
      (node (ref "J2") (pin "7") (pinfunction "7_7") (pintype "passive"))
    )
    (net (code "97") (name "unconnected-(J2-Pad8)") (class "Default")
      (node (ref "J2") (pin "8") (pinfunction "8_8") (pintype "passive"))
    )
    (net (code "98") (name "unconnected-(J2-Pad9)") (class "Default")
      (node (ref "J2") (pin "9") (pinfunction "9_9") (pintype "passive"))
    )
    (net (code "99") (name "unconnected-(J2-Pad10)") (class "Default")
      (node (ref "J2") (pin "10") (pinfunction "10_10") (pintype "passive"))
    )
    (net (code "100") (name "unconnected-(J2-Pad11)") (class "Default")
      (node (ref "J2") (pin "11") (pinfunction "11_11") (pintype "passive"))
    )
    (net (code "101") (name "unconnected-(J2-Pad12)") (class "Default")
      (node (ref "J2") (pin "12") (pinfunction "12_12") (pintype "passive"))
    )
    (net (code "102") (name "unconnected-(J2-Pad13)") (class "Default")
      (node (ref "J2") (pin "13") (pinfunction "13_13") (pintype "passive"))
    )
    (net (code "103") (name "unconnected-(J2-Pad14)") (class "Default")
      (node (ref "J2") (pin "14") (pinfunction "14_14") (pintype "passive"))
    )
    (net (code "104") (name "unconnected-(J2-Pad15)") (class "Default")
      (node (ref "J2") (pin "15") (pinfunction "15_15") (pintype "passive"))
    )
    (net (code "105") (name "unconnected-(J2-Pad16)") (class "Default")
      (node (ref "J2") (pin "16") (pinfunction "16_16") (pintype "passive"))
    )
    (net (code "106") (name "unconnected-(J2-Pad17)") (class "Default")
      (node (ref "J2") (pin "17") (pinfunction "17_17") (pintype "passive"))
    )
    (net (code "107") (name "unconnected-(J2-Pad18)") (class "Default")
      (node (ref "J2") (pin "18") (pinfunction "18_18") (pintype "passive"))
    )
    (net (code "108") (name "unconnected-(J2-Pad19)") (class "Default")
      (node (ref "J2") (pin "19") (pinfunction "19_19") (pintype "passive"))
    )
    (net (code "109") (name "unconnected-(J2-Pad20)") (class "Default")
      (node (ref "J2") (pin "20") (pinfunction "20_20") (pintype "passive"))
    )
    (net (code "110") (name "unconnected-(J2-Pad21)") (class "Default")
      (node (ref "J2") (pin "21") (pinfunction "21_21") (pintype "passive"))
    )
    (net (code "111") (name "unconnected-(J2-Pad22)") (class "Default")
      (node (ref "J2") (pin "22") (pinfunction "22_22") (pintype "passive"))
    )
    (net (code "112") (name "unconnected-(J2-Pad23)") (class "Default")
      (node (ref "J2") (pin "23") (pinfunction "23_23") (pintype "passive"))
    )
    (net (code "113") (name "unconnected-(J2-Pad24)") (class "Default")
      (node (ref "J2") (pin "24") (pinfunction "24_24") (pintype "passive"))
    )
    (net (code "114") (name "unconnected-(J2-Pad25)") (class "Default")
      (node (ref "J2") (pin "25") (pinfunction "25_25") (pintype "passive"))
    )
    (net (code "115") (name "unconnected-(J2-Pad26)") (class "Default")
      (node (ref "J2") (pin "26") (pinfunction "26_26") (pintype "passive"))
    )
  )
)
